# tiny.net
KiCad netlist of a schematic drawn in EAGLE
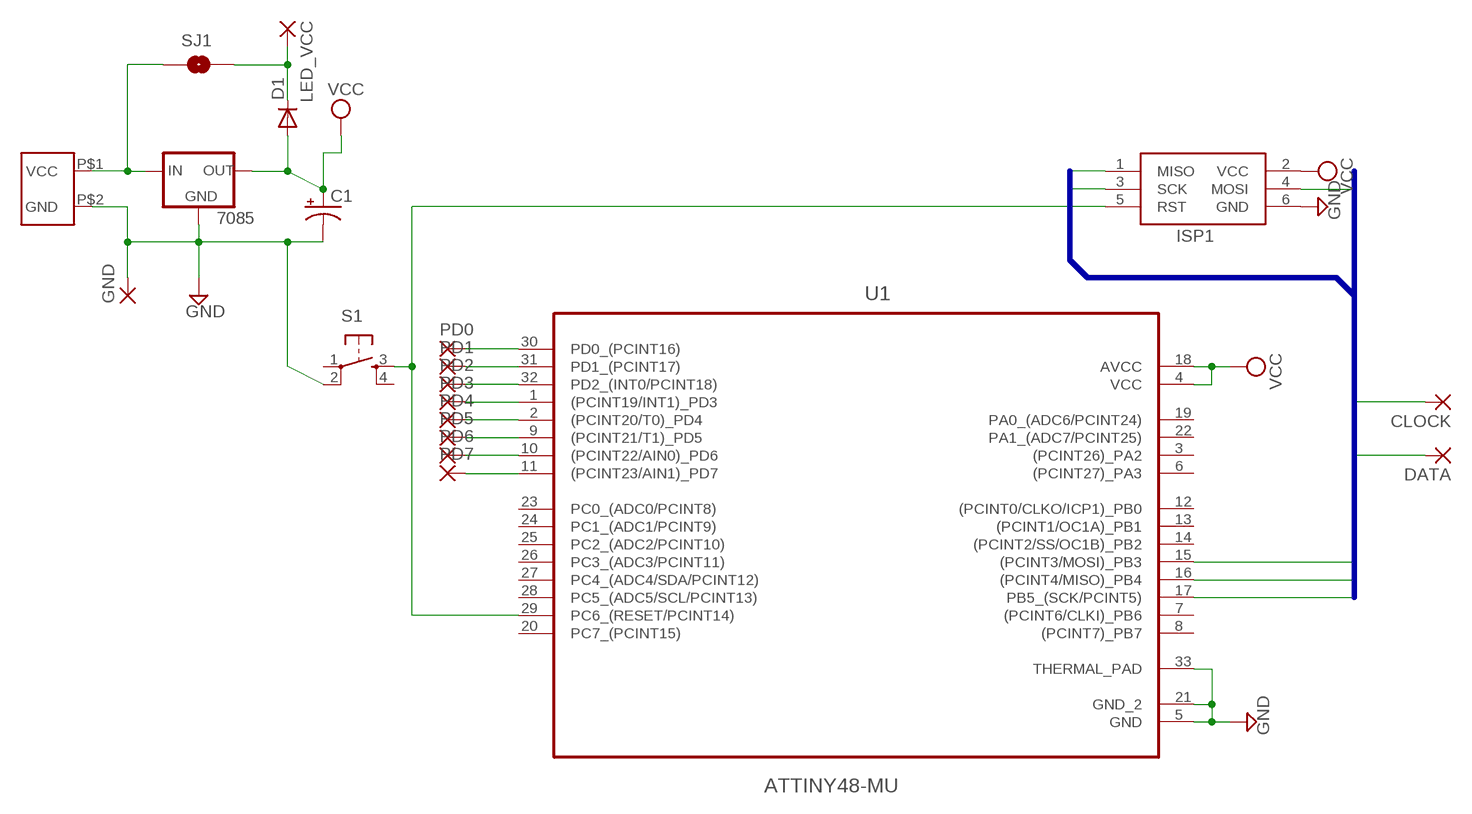
[diagram p0: schematic, sheet 1]

(export (version "E")
  (design (tool "Eeschema 10.0.6"))
  (components
    (comp (ref "7085")
      (value "V_REG_78XXSIDE")
      (footprint "eagle-import:78XXL")
      (libsource (lib "eagle-import") (part "V_REG_78XXSIDE"))
    )
    (comp (ref "C1")
      (value "CPOL-USE2.5-6")
      (footprint "eagle-import:E2,5-6")
      (libsource (lib "eagle-import") (part "CPOL-USE2.5-6"))
    )
    (comp (ref "CLOCK")
      (value "2,54/1,0")
      (footprint "eagle-import:2,54_1,0")
      (libsource (lib "eagle-import") (part "2,54/1,0"))
    )
    (comp (ref "D1")
      (value "DIODE1N4148")
      (footprint "eagle-import:DIODE-1N4148")
      (libsource (lib "eagle-import") (part "DIODE1N4148"))
    )
    (comp (ref "DATA")
      (value "2,54/1,0")
      (footprint "eagle-import:2,54_1,0")
      (libsource (lib "eagle-import") (part "2,54/1,0"))
    )
    (comp (ref "GND")
      (value "2,54/1,0")
      (footprint "eagle-import:2,54_1,0")
      (libsource (lib "eagle-import") (part "2,54/1,0"))
    )
    (comp (ref "ISP1")
      (value "AVRISP-6")
      (footprint "eagle-import:AVRISP")
      (libsource (lib "eagle-import") (part "AVRISP-6"))
    )
    (comp (ref "LED_VCC")
      (value "2,54/1,0")
      (footprint "eagle-import:2,54_1,0")
      (libsource (lib "eagle-import") (part "2,54/1,0"))
    )
    (comp (ref "PD0")
      (value "1,6/0,9")
      (footprint "eagle-import:1,6_0,9")
      (libsource (lib "eagle-import") (part "1,6/0,9"))
    )
    (comp (ref "PD1")
      (value "1,6/0,9")
      (footprint "eagle-import:1,6_0,9")
      (libsource (lib "eagle-import") (part "1,6/0,9"))
    )
    (comp (ref "PD2")
      (value "1,6/0,9")
      (footprint "eagle-import:1,6_0,9")
      (libsource (lib "eagle-import") (part "1,6/0,9"))
    )
    (comp (ref "PD3")
      (value "1,6/0,9")
      (footprint "eagle-import:1,6_0,9")
      (libsource (lib "eagle-import") (part "1,6/0,9"))
    )
    (comp (ref "PD4")
      (value "1,6/0,9")
      (footprint "eagle-import:1,6_0,9")
      (libsource (lib "eagle-import") (part "1,6/0,9"))
    )
    (comp (ref "PD5")
      (value "1,6/0,9")
      (footprint "eagle-import:1,6_0,9")
      (libsource (lib "eagle-import") (part "1,6/0,9"))
    )
    (comp (ref "PD6")
      (value "1,6/0,9")
      (footprint "eagle-import:1,6_0,9")
      (libsource (lib "eagle-import") (part "1,6/0,9"))
    )
    (comp (ref "PD7")
      (value "1,6/0,9")
      (footprint "eagle-import:1,6_0,9")
      (libsource (lib "eagle-import") (part "1,6/0,9"))
    )
    (comp (ref "S1")
      (value "TAC_SWITCHSMD")
      (footprint "eagle-import:TACTILE_SWITCH_SMD")
      (libsource (lib "eagle-import") (part "TAC_SWITCHSMD"))
    )
    (comp (ref "SJ1")
      (value "LED_VCC = VCC")
      (footprint "eagle-import:SJ_2S-NO")
      (libsource (lib "eagle-import") (part "SOLDERJUMPERNO"))
    )
    (comp (ref "U1")
      (value "ATTINY48-MU")
      (footprint "eagle-import:QFN50P500X500X100-33N")
      (libsource (lib "eagle-import") (part "ATTINY48-MU"))
    )
    (comp (ref "VCC")
      (value "OSTOQ023251")
      (footprint "eagle-import:OSTOQ023251")
      (libsource (lib "eagle-import") (part "OSTOQ023251"))
    )
  )
  (nets
    (net (code "1") (name "/MISO") (class "Default")
      (node (ref "ISP1") (pin "1") (pinfunction "MISO_1") (pintype "input"))
      (node (ref "U1") (pin "16") (pinfunction "(PCINT4/MISO)_PB4_16") (pintype "bidirectional"))
    )
    (net (code "2") (name "/MOSI") (class "Default")
      (node (ref "DATA") (pin "1") (pinfunction "P_1") (pintype "passive"))
      (node (ref "ISP1") (pin "4") (pinfunction "MOSI_4") (pintype "output"))
      (node (ref "U1") (pin "15") (pinfunction "(PCINT3/MOSI)_PB3_15") (pintype "bidirectional"))
    )
    (net (code "3") (name "/SCK") (class "Default")
      (node (ref "CLOCK") (pin "1") (pinfunction "P_1") (pintype "passive"))
      (node (ref "ISP1") (pin "3") (pinfunction "SCK_3") (pintype "output"))
      (node (ref "U1") (pin "17") (pinfunction "PB5_(SCK/PCINT5)_17") (pintype "bidirectional"))
    )
    (net (code "4") (name "GND") (class "Default")
      (node (ref "7085") (pin "GND") (pinfunction "GND_GND") (pintype "input"))
      (node (ref "C1") (pin "-") (pinfunction "-_-") (pintype "passive"))
      (node (ref "GND") (pin "1") (pinfunction "P_1") (pintype "passive"))
      (node (ref "ISP1") (pin "6") (pinfunction "GND_6") (pintype "power_in"))
      (node (ref "S1") (pin "2") (pinfunction "2_2") (pintype "passive"))
      (node (ref "U1") (pin "21") (pinfunction "GND_2_21") (pintype "passive"))
      (node (ref "U1") (pin "33") (pinfunction "THERMAL_PAD_33") (pintype "passive"))
      (node (ref "U1") (pin "5") (pinfunction "GND_5") (pintype "passive"))
      (node (ref "VCC") (pin "P$2") (pinfunction "GND_P$2") (pintype "bidirectional"))
    )
    (net (code "5") (name "Net-(ISP1-RST)") (class "Default")
      (node (ref "ISP1") (pin "5") (pinfunction "RST_5") (pintype "output"))
      (node (ref "S1") (pin "3") (pinfunction "3_3") (pintype "passive"))
      (node (ref "U1") (pin "29") (pinfunction "PC6_(RESET/PCINT14)_29") (pintype "bidirectional"))
    )
    (net (code "6") (name "Net-(LED_VCC-P)") (class "Default")
      (node (ref "D1") (pin "C") (pinfunction "C_C") (pintype "passive"))
      (node (ref "LED_VCC") (pin "1") (pinfunction "P_1") (pintype "passive"))
      (node (ref "SJ1") (pin "2") (pinfunction "2_2") (pintype "passive"))
    )
    (net (code "7") (name "Net-(PD0-P)") (class "Default")
      (node (ref "PD0") (pin "1") (pinfunction "P_1") (pintype "passive"))
      (node (ref "U1") (pin "30") (pinfunction "PD0_(PCINT16)_30") (pintype "bidirectional"))
    )
    (net (code "8") (name "Net-(PD1-P)") (class "Default")
      (node (ref "PD1") (pin "1") (pinfunction "P_1") (pintype "passive"))
      (node (ref "U1") (pin "31") (pinfunction "PD1_(PCINT17)_31") (pintype "bidirectional"))
    )
    (net (code "9") (name "Net-(PD2-P)") (class "Default")
      (node (ref "PD2") (pin "1") (pinfunction "P_1") (pintype "passive"))
      (node (ref "U1") (pin "32") (pinfunction "PD2_(INT0/PCINT18)_32") (pintype "bidirectional"))
    )
    (net (code "10") (name "Net-(PD3-P)") (class "Default")
      (node (ref "PD3") (pin "1") (pinfunction "P_1") (pintype "passive"))
      (node (ref "U1") (pin "1") (pinfunction "(PCINT19/INT1)_PD3_1") (pintype "bidirectional"))
    )
    (net (code "11") (name "Net-(PD4-P)") (class "Default")
      (node (ref "PD4") (pin "1") (pinfunction "P_1") (pintype "passive"))
      (node (ref "U1") (pin "2") (pinfunction "(PCINT20/T0)_PD4_2") (pintype "bidirectional"))
    )
    (net (code "12") (name "Net-(PD5-P)") (class "Default")
      (node (ref "PD5") (pin "1") (pinfunction "P_1") (pintype "passive"))
      (node (ref "U1") (pin "9") (pinfunction "(PCINT21/T1)_PD5_9") (pintype "bidirectional"))
    )
    (net (code "13") (name "Net-(PD6-P)") (class "Default")
      (node (ref "PD6") (pin "1") (pinfunction "P_1") (pintype "passive"))
      (node (ref "U1") (pin "10") (pinfunction "(PCINT22/AIN0)_PD6_10") (pintype "bidirectional"))
    )
    (net (code "14") (name "Net-(PD7-P)") (class "Default")
      (node (ref "PD7") (pin "1") (pinfunction "P_1") (pintype "passive"))
      (node (ref "U1") (pin "11") (pinfunction "(PCINT23/AIN1)_PD7_11") (pintype "bidirectional"))
    )
    (net (code "15") (name "Net-(VCC-VCC)") (class "Default")
      (node (ref "7085") (pin "IN") (pinfunction "IN_IN") (pintype "input"))
      (node (ref "SJ1") (pin "1") (pinfunction "1_1") (pintype "passive"))
      (node (ref "VCC") (pin "P$1") (pinfunction "VCC_P$1") (pintype "bidirectional"))
    )
    (net (code "16") (name "VCC") (class "Default")
      (node (ref "7085") (pin "OUT") (pinfunction "OUT_OUT") (pintype "output"))
      (node (ref "C1") (pin "+") (pinfunction "+_+") (pintype "passive"))
      (node (ref "D1") (pin "A") (pinfunction "A_A") (pintype "passive"))
      (node (ref "ISP1") (pin "2") (pinfunction "VCC_2") (pintype "power_in"))
      (node (ref "U1") (pin "18") (pinfunction "AVCC_18") (pintype "power_in"))
      (node (ref "U1") (pin "4") (pinfunction "VCC_4") (pintype "power_in"))
    )
    (net (code "17") (name "unconnected-(S1-Pad1)") (class "Default")
      (node (ref "S1") (pin "1") (pinfunction "1_1") (pintype "passive"))
    )
    (net (code "18") (name "unconnected-(S1-Pad4)") (class "Default")
      (node (ref "S1") (pin "4") (pinfunction "4_4") (pintype "passive"))
    )
    (net (code "19") (name "unconnected-(U1-(PCINT0{slash}CLKO{slash}ICP1)_PB0-Pad12)") (class "Default")
      (node (ref "U1") (pin "12") (pinfunction "(PCINT0/CLKO/ICP1)_PB0_12") (pintype "bidirectional"))
    )
    (net (code "20") (name "unconnected-(U1-(PCINT1{slash}OC1A)_PB1-Pad13)") (class "Default")
      (node (ref "U1") (pin "13") (pinfunction "(PCINT1/OC1A)_PB1_13") (pintype "bidirectional"))
    )
    (net (code "21") (name "unconnected-(U1-(PCINT2{slash}SS{slash}OC1B)_PB2-Pad14)") (class "Default")
      (node (ref "U1") (pin "14") (pinfunction "(PCINT2/SS/OC1B)_PB2_14") (pintype "bidirectional"))
    )
    (net (code "22") (name "unconnected-(U1-(PCINT6{slash}CLKI)_PB6-Pad7)") (class "Default")
      (node (ref "U1") (pin "7") (pinfunction "(PCINT6/CLKI)_PB6_7") (pintype "bidirectional"))
    )
    (net (code "23") (name "unconnected-(U1-(PCINT7)_PB7-Pad8)") (class "Default")
      (node (ref "U1") (pin "8") (pinfunction "(PCINT7)_PB7_8") (pintype "bidirectional"))
    )
    (net (code "24") (name "unconnected-(U1-(PCINT26)_PA2-Pad3)") (class "Default")
      (node (ref "U1") (pin "3") (pinfunction "(PCINT26)_PA2_3") (pintype "bidirectional"))
    )
    (net (code "25") (name "unconnected-(U1-(PCINT27)_PA3-Pad6)") (class "Default")
      (node (ref "U1") (pin "6") (pinfunction "(PCINT27)_PA3_6") (pintype "bidirectional"))
    )
    (net (code "26") (name "unconnected-(U1-PA0_(ADC6{slash}PCINT24)-Pad19)") (class "Default")
      (node (ref "U1") (pin "19") (pinfunction "PA0_(ADC6/PCINT24)_19") (pintype "bidirectional"))
    )
    (net (code "27") (name "unconnected-(U1-PA1_(ADC7{slash}PCINT25)-Pad22)") (class "Default")
      (node (ref "U1") (pin "22") (pinfunction "PA1_(ADC7/PCINT25)_22") (pintype "bidirectional"))
    )
    (net (code "28") (name "unconnected-(U1-PC0_(ADC0{slash}PCINT8)-Pad23)") (class "Default")
      (node (ref "U1") (pin "23") (pinfunction "PC0_(ADC0/PCINT8)_23") (pintype "bidirectional"))
    )
    (net (code "29") (name "unconnected-(U1-PC1_(ADC1{slash}PCINT9)-Pad24)") (class "Default")
      (node (ref "U1") (pin "24") (pinfunction "PC1_(ADC1/PCINT9)_24") (pintype "bidirectional"))
    )
    (net (code "30") (name "unconnected-(U1-PC2_(ADC2{slash}PCINT10)-Pad25)") (class "Default")
      (node (ref "U1") (pin "25") (pinfunction "PC2_(ADC2/PCINT10)_25") (pintype "bidirectional"))
    )
    (net (code "31") (name "unconnected-(U1-PC3_(ADC3{slash}PCINT11)-Pad26)") (class "Default")
      (node (ref "U1") (pin "26") (pinfunction "PC3_(ADC3/PCINT11)_26") (pintype "bidirectional"))
    )
    (net (code "32") (name "unconnected-(U1-PC4_(ADC4{slash}SDA{slash}PCINT12)-Pad27)") (class "Default")
      (node (ref "U1") (pin "27") (pinfunction "PC4_(ADC4/SDA/PCINT12)_27") (pintype "bidirectional"))
    )
    (net (code "33") (name "unconnected-(U1-PC5_(ADC5{slash}SCL{slash}PCINT13)-Pad28)") (class "Default")
      (node (ref "U1") (pin "28") (pinfunction "PC5_(ADC5/SCL/PCINT13)_28") (pintype "bidirectional"))
    )
    (net (code "34") (name "unconnected-(U1-PC7_(PCINT15)-Pad20)") (class "Default")
      (node (ref "U1") (pin "20") (pinfunction "PC7_(PCINT15)_20") (pintype "bidirectional"))
    )
  )
)
